# SwitchMult_R2_0.net
KiCad netlist of a schematic drawn in EAGLE
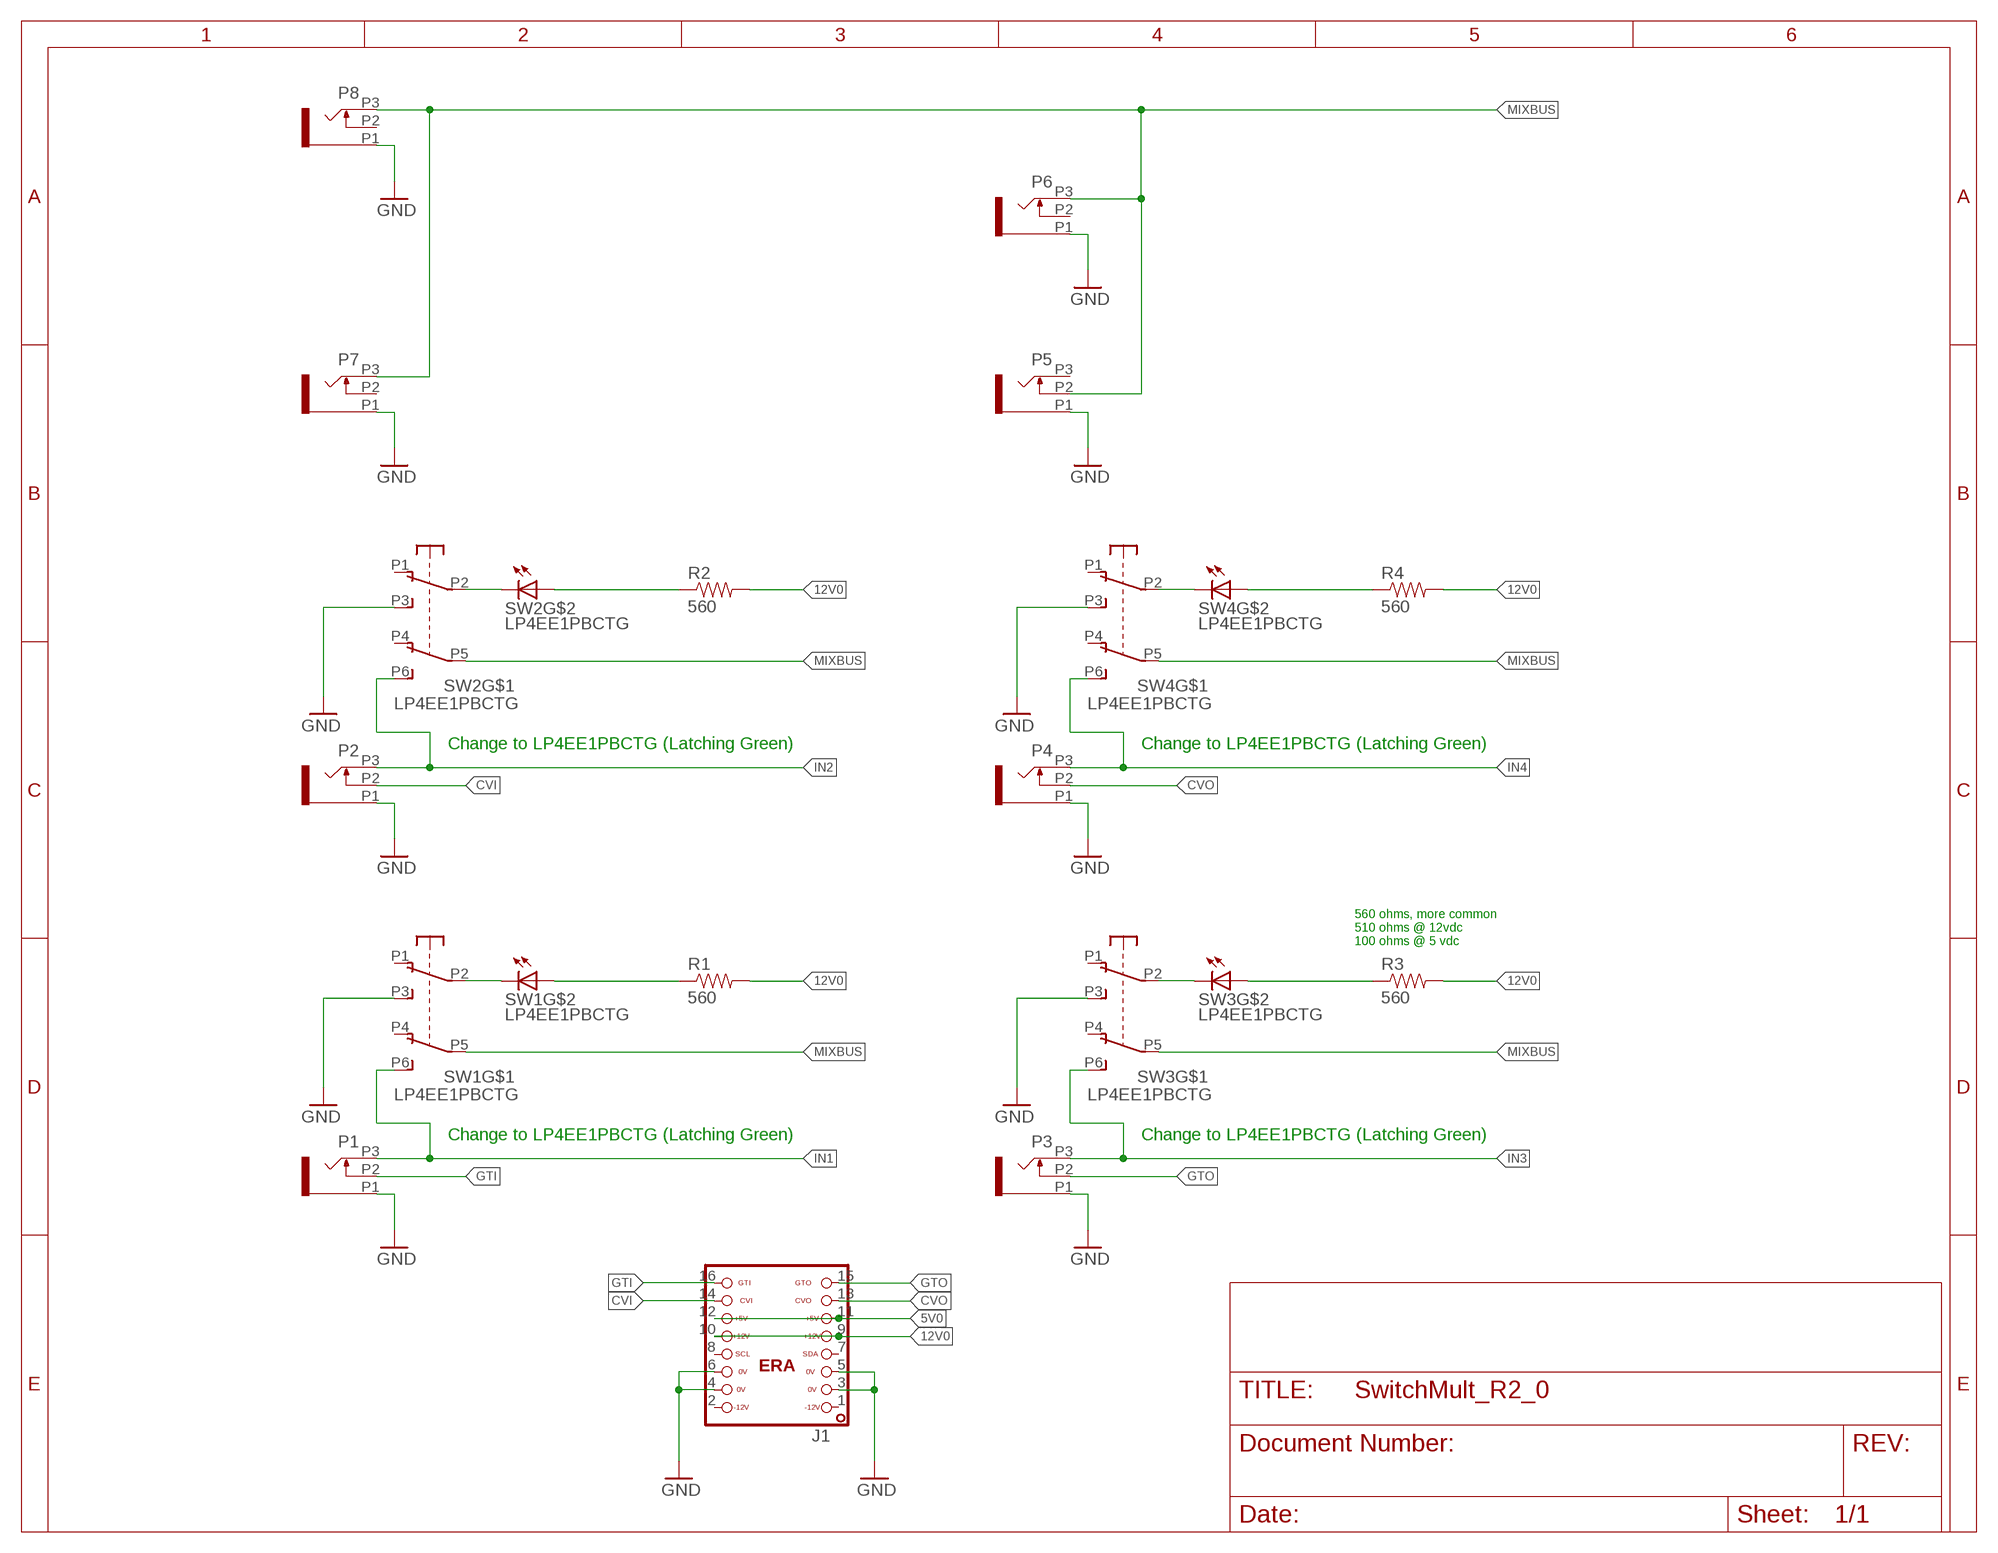
[diagram p0: schematic, sheet 1]

(export (version "E")
  (design (tool "Eeschema 10.0.6"))
  (components
    (comp (ref "J1")
      (value "ERA-SHROUD")
      (footprint "eagle-import:ERA")
      (libsource (lib "eagle-import") (part "ERA-SHROUD"))
    )
    (comp (ref "P1")
      (value "PJ301_THONKICONN6")
      (footprint "eagle-import:WQP_PJ_301M6")
      (libsource (lib "eagle-import") (part "PJ301_THONKICONN6"))
    )
    (comp (ref "P2")
      (value "PJ301_THONKICONN6")
      (footprint "eagle-import:WQP_PJ_301M6")
      (libsource (lib "eagle-import") (part "PJ301_THONKICONN6"))
    )
    (comp (ref "P3")
      (value "PJ301_THONKICONN6")
      (footprint "eagle-import:WQP_PJ_301M6")
      (libsource (lib "eagle-import") (part "PJ301_THONKICONN6"))
    )
    (comp (ref "P4")
      (value "PJ301_THONKICONN6")
      (footprint "eagle-import:WQP_PJ_301M6")
      (libsource (lib "eagle-import") (part "PJ301_THONKICONN6"))
    )
    (comp (ref "P5")
      (value "PJ301_THONKICONN6")
      (footprint "eagle-import:WQP_PJ_301M6")
      (libsource (lib "eagle-import") (part "PJ301_THONKICONN6"))
    )
    (comp (ref "P6")
      (value "PJ301_THONKICONN6")
      (footprint "eagle-import:WQP_PJ_301M6")
      (libsource (lib "eagle-import") (part "PJ301_THONKICONN6"))
    )
    (comp (ref "P7")
      (value "PJ301_THONKICONN6")
      (footprint "eagle-import:WQP_PJ_301M6")
      (libsource (lib "eagle-import") (part "PJ301_THONKICONN6"))
    )
    (comp (ref "P8")
      (value "PJ301_THONKICONN6")
      (footprint "eagle-import:WQP_PJ_301M6")
      (libsource (lib "eagle-import") (part "PJ301_THONKICONN6"))
    )
    (comp (ref "R1")
      (value "560")
      (footprint "eagle-import:AXIAL-0.4")
      (libsource (lib "eagle-import") (part "RESISTORPTH-1/4W"))
    )
    (comp (ref "R2")
      (value "560")
      (footprint "eagle-import:AXIAL-0.4")
      (libsource (lib "eagle-import") (part "RESISTORPTH-1/4W"))
    )
    (comp (ref "R3")
      (value "560")
      (footprint "eagle-import:AXIAL-0.4")
      (libsource (lib "eagle-import") (part "RESISTORPTH-1/4W"))
    )
    (comp (ref "R4")
      (value "560")
      (footprint "eagle-import:AXIAL-0.4")
      (libsource (lib "eagle-import") (part "RESISTORPTH-1/4W"))
    )
    (comp (ref "SW1")
      (value "LP4EE1PBCTG")
      (footprint "eagle-import:LP4OA1PBCT")
      (libsource (lib "eagle-import") (part "LP4OA1PBCT"))
    )
    (comp (ref "SW2")
      (value "LP4EE1PBCTG")
      (footprint "eagle-import:LP4OA1PBCT")
      (libsource (lib "eagle-import") (part "LP4OA1PBCT"))
    )
    (comp (ref "SW3")
      (value "LP4EE1PBCTG")
      (footprint "eagle-import:LP4OA1PBCT")
      (libsource (lib "eagle-import") (part "LP4OA1PBCT"))
    )
    (comp (ref "SW4")
      (value "LP4EE1PBCTG")
      (footprint "eagle-import:LP4OA1PBCT")
      (libsource (lib "eagle-import") (part "LP4OA1PBCT"))
    )
  )
  (nets
    (net (code "1") (name "5V0") (class "Default")
      (node (ref "J1") (pin "11") (pinfunction "11_11") (pintype "passive"))
      (node (ref "J1") (pin "12") (pinfunction "12_12") (pintype "passive"))
    )
    (net (code "2") (name "12V0") (class "Default")
      (node (ref "J1") (pin "10") (pinfunction "10_10") (pintype "passive"))
      (node (ref "J1") (pin "9") (pinfunction "9_9") (pintype "passive"))
      (node (ref "R1") (pin "P$2") (pinfunction "2_P$2") (pintype "passive"))
      (node (ref "R2") (pin "P$2") (pinfunction "2_P$2") (pintype "passive"))
      (node (ref "R3") (pin "P$2") (pinfunction "2_P$2") (pintype "passive"))
      (node (ref "R4") (pin "P$2") (pinfunction "2_P$2") (pintype "passive"))
    )
    (net (code "3") (name "CVI") (class "Default")
      (node (ref "J1") (pin "14") (pinfunction "14_14") (pintype "passive"))
      (node (ref "P2") (pin "P2") (pinfunction "2_P2") (pintype "passive"))
    )
    (net (code "4") (name "CVO") (class "Default")
      (node (ref "J1") (pin "13") (pinfunction "13_13") (pintype "passive"))
      (node (ref "P4") (pin "P2") (pinfunction "2_P2") (pintype "passive"))
    )
    (net (code "5") (name "GND") (class "Default")
      (node (ref "J1") (pin "3") (pinfunction "3_3") (pintype "passive"))
      (node (ref "J1") (pin "4") (pinfunction "4_4") (pintype "passive"))
      (node (ref "J1") (pin "5") (pinfunction "5_5") (pintype "passive"))
      (node (ref "J1") (pin "6") (pinfunction "6_6") (pintype "passive"))
      (node (ref "P1") (pin "P1") (pinfunction "1_P1") (pintype "passive"))
      (node (ref "P2") (pin "P1") (pinfunction "1_P1") (pintype "passive"))
      (node (ref "P3") (pin "P1") (pinfunction "1_P1") (pintype "passive"))
      (node (ref "P4") (pin "P1") (pinfunction "1_P1") (pintype "passive"))
      (node (ref "P5") (pin "P1") (pinfunction "1_P1") (pintype "passive"))
      (node (ref "P6") (pin "P1") (pinfunction "1_P1") (pintype "passive"))
      (node (ref "P7") (pin "P1") (pinfunction "1_P1") (pintype "passive"))
      (node (ref "P8") (pin "P1") (pinfunction "1_P1") (pintype "passive"))
      (node (ref "SW1") (pin "P3") (pinfunction "A3_P3") (pintype "passive"))
      (node (ref "SW2") (pin "P3") (pinfunction "A3_P3") (pintype "passive"))
      (node (ref "SW3") (pin "P3") (pinfunction "A3_P3") (pintype "passive"))
      (node (ref "SW4") (pin "P3") (pinfunction "A3_P3") (pintype "passive"))
    )
    (net (code "6") (name "GTI") (class "Default")
      (node (ref "J1") (pin "16") (pinfunction "16_16") (pintype "passive"))
      (node (ref "P1") (pin "P2") (pinfunction "2_P2") (pintype "passive"))
    )
    (net (code "7") (name "GTO") (class "Default")
      (node (ref "J1") (pin "15") (pinfunction "15_15") (pintype "passive"))
      (node (ref "P3") (pin "P2") (pinfunction "2_P2") (pintype "passive"))
    )
    (net (code "8") (name "IN1") (class "Default")
      (node (ref "P1") (pin "P3") (pinfunction "3_P3") (pintype "passive"))
      (node (ref "SW1") (pin "P6") (pinfunction "B3_P6") (pintype "passive"))
    )
    (net (code "9") (name "IN2") (class "Default")
      (node (ref "P2") (pin "P3") (pinfunction "3_P3") (pintype "passive"))
      (node (ref "SW2") (pin "P6") (pinfunction "B3_P6") (pintype "passive"))
    )
    (net (code "10") (name "IN3") (class "Default")
      (node (ref "P3") (pin "P3") (pinfunction "3_P3") (pintype "passive"))
      (node (ref "SW3") (pin "P6") (pinfunction "B3_P6") (pintype "passive"))
    )
    (net (code "11") (name "IN4") (class "Default")
      (node (ref "P4") (pin "P3") (pinfunction "3_P3") (pintype "passive"))
      (node (ref "SW4") (pin "P6") (pinfunction "B3_P6") (pintype "passive"))
    )
    (net (code "12") (name "MIXBUS") (class "Default")
      (node (ref "P5") (pin "P2") (pinfunction "2_P2") (pintype "passive"))
      (node (ref "P6") (pin "P3") (pinfunction "3_P3") (pintype "passive"))
      (node (ref "P7") (pin "P3") (pinfunction "3_P3") (pintype "passive"))
      (node (ref "P8") (pin "P3") (pinfunction "3_P3") (pintype "passive"))
      (node (ref "SW1") (pin "P5") (pinfunction "B2_P5") (pintype "passive"))
      (node (ref "SW2") (pin "P5") (pinfunction "B2_P5") (pintype "passive"))
      (node (ref "SW3") (pin "P5") (pinfunction "B2_P5") (pintype "passive"))
      (node (ref "SW4") (pin "P5") (pinfunction "B2_P5") (pintype "passive"))
    )
    (net (code "13") (name "Net-(R1-1)") (class "Default")
      (node (ref "R1") (pin "P$1") (pinfunction "1_P$1") (pintype "passive"))
      (node (ref "SW1") (pin "L1") (pinfunction "L1_L1") (pintype "passive"))
    )
    (net (code "14") (name "Net-(R2-1)") (class "Default")
      (node (ref "R2") (pin "P$1") (pinfunction "1_P$1") (pintype "passive"))
      (node (ref "SW2") (pin "L1") (pinfunction "L1_L1") (pintype "passive"))
    )
    (net (code "15") (name "Net-(R3-1)") (class "Default")
      (node (ref "R3") (pin "P$1") (pinfunction "1_P$1") (pintype "passive"))
      (node (ref "SW3") (pin "L1") (pinfunction "L1_L1") (pintype "passive"))
    )
    (net (code "16") (name "Net-(R4-1)") (class "Default")
      (node (ref "R4") (pin "P$1") (pinfunction "1_P$1") (pintype "passive"))
      (node (ref "SW4") (pin "L1") (pinfunction "L1_L1") (pintype "passive"))
    )
    (net (code "17") (name "Net-(SW1A-A2)") (class "Default")
      (node (ref "SW1") (pin "L2") (pinfunction "L2_L2") (pintype "passive"))
      (node (ref "SW1") (pin "P2") (pinfunction "A2_P2") (pintype "passive"))
    )
    (net (code "18") (name "Net-(SW2A-A2)") (class "Default")
      (node (ref "SW2") (pin "L2") (pinfunction "L2_L2") (pintype "passive"))
      (node (ref "SW2") (pin "P2") (pinfunction "A2_P2") (pintype "passive"))
    )
    (net (code "19") (name "Net-(SW3A-A2)") (class "Default")
      (node (ref "SW3") (pin "L2") (pinfunction "L2_L2") (pintype "passive"))
      (node (ref "SW3") (pin "P2") (pinfunction "A2_P2") (pintype "passive"))
    )
    (net (code "20") (name "Net-(SW4A-A2)") (class "Default")
      (node (ref "SW4") (pin "L2") (pinfunction "L2_L2") (pintype "passive"))
      (node (ref "SW4") (pin "P2") (pinfunction "A2_P2") (pintype "passive"))
    )
    (net (code "21") (name "unconnected-(J1-Pad1)") (class "Default")
      (node (ref "J1") (pin "1") (pinfunction "1_1") (pintype "passive"))
    )
    (net (code "22") (name "unconnected-(J1-Pad2)") (class "Default")
      (node (ref "J1") (pin "2") (pinfunction "2_2") (pintype "passive"))
    )
    (net (code "23") (name "unconnected-(J1-Pad7)") (class "Default")
      (node (ref "J1") (pin "7") (pinfunction "7_7") (pintype "passive"))
    )
    (net (code "24") (name "unconnected-(J1-Pad8)") (class "Default")
      (node (ref "J1") (pin "8") (pinfunction "8_8") (pintype "passive"))
    )
    (net (code "25") (name "unconnected-(P5-3-PadP3)") (class "Default")
      (node (ref "P5") (pin "P3") (pinfunction "3_P3") (pintype "passive"))
    )
    (net (code "26") (name "unconnected-(P6-2-PadP2)") (class "Default")
      (node (ref "P6") (pin "P2") (pinfunction "2_P2") (pintype "passive"))
    )
    (net (code "27") (name "unconnected-(P7-2-PadP2)") (class "Default")
      (node (ref "P7") (pin "P2") (pinfunction "2_P2") (pintype "passive"))
    )
    (net (code "28") (name "unconnected-(P8-2-PadP2)") (class "Default")
      (node (ref "P8") (pin "P2") (pinfunction "2_P2") (pintype "passive"))
    )
    (net (code "29") (name "unconnected-(SW1A-A1-PadP1)") (class "Default")
      (node (ref "SW1") (pin "P1") (pinfunction "A1_P1") (pintype "passive"))
    )
    (net (code "30") (name "unconnected-(SW1A-B1-PadP4)") (class "Default")
      (node (ref "SW1") (pin "P4") (pinfunction "B1_P4") (pintype "passive"))
    )
    (net (code "31") (name "unconnected-(SW2A-A1-PadP1)") (class "Default")
      (node (ref "SW2") (pin "P1") (pinfunction "A1_P1") (pintype "passive"))
    )
    (net (code "32") (name "unconnected-(SW2A-B1-PadP4)") (class "Default")
      (node (ref "SW2") (pin "P4") (pinfunction "B1_P4") (pintype "passive"))
    )
    (net (code "33") (name "unconnected-(SW3A-A1-PadP1)") (class "Default")
      (node (ref "SW3") (pin "P1") (pinfunction "A1_P1") (pintype "passive"))
    )
    (net (code "34") (name "unconnected-(SW3A-B1-PadP4)") (class "Default")
      (node (ref "SW3") (pin "P4") (pinfunction "B1_P4") (pintype "passive"))
    )
    (net (code "35") (name "unconnected-(SW4A-A1-PadP1)") (class "Default")
      (node (ref "SW4") (pin "P1") (pinfunction "A1_P1") (pintype "passive"))
    )
    (net (code "36") (name "unconnected-(SW4A-B1-PadP4)") (class "Default")
      (node (ref "SW4") (pin "P4") (pinfunction "B1_P4") (pintype "passive"))
    )
  )
)
